# mainboard.net
KiCad netlist of a schematic drawn in EAGLE
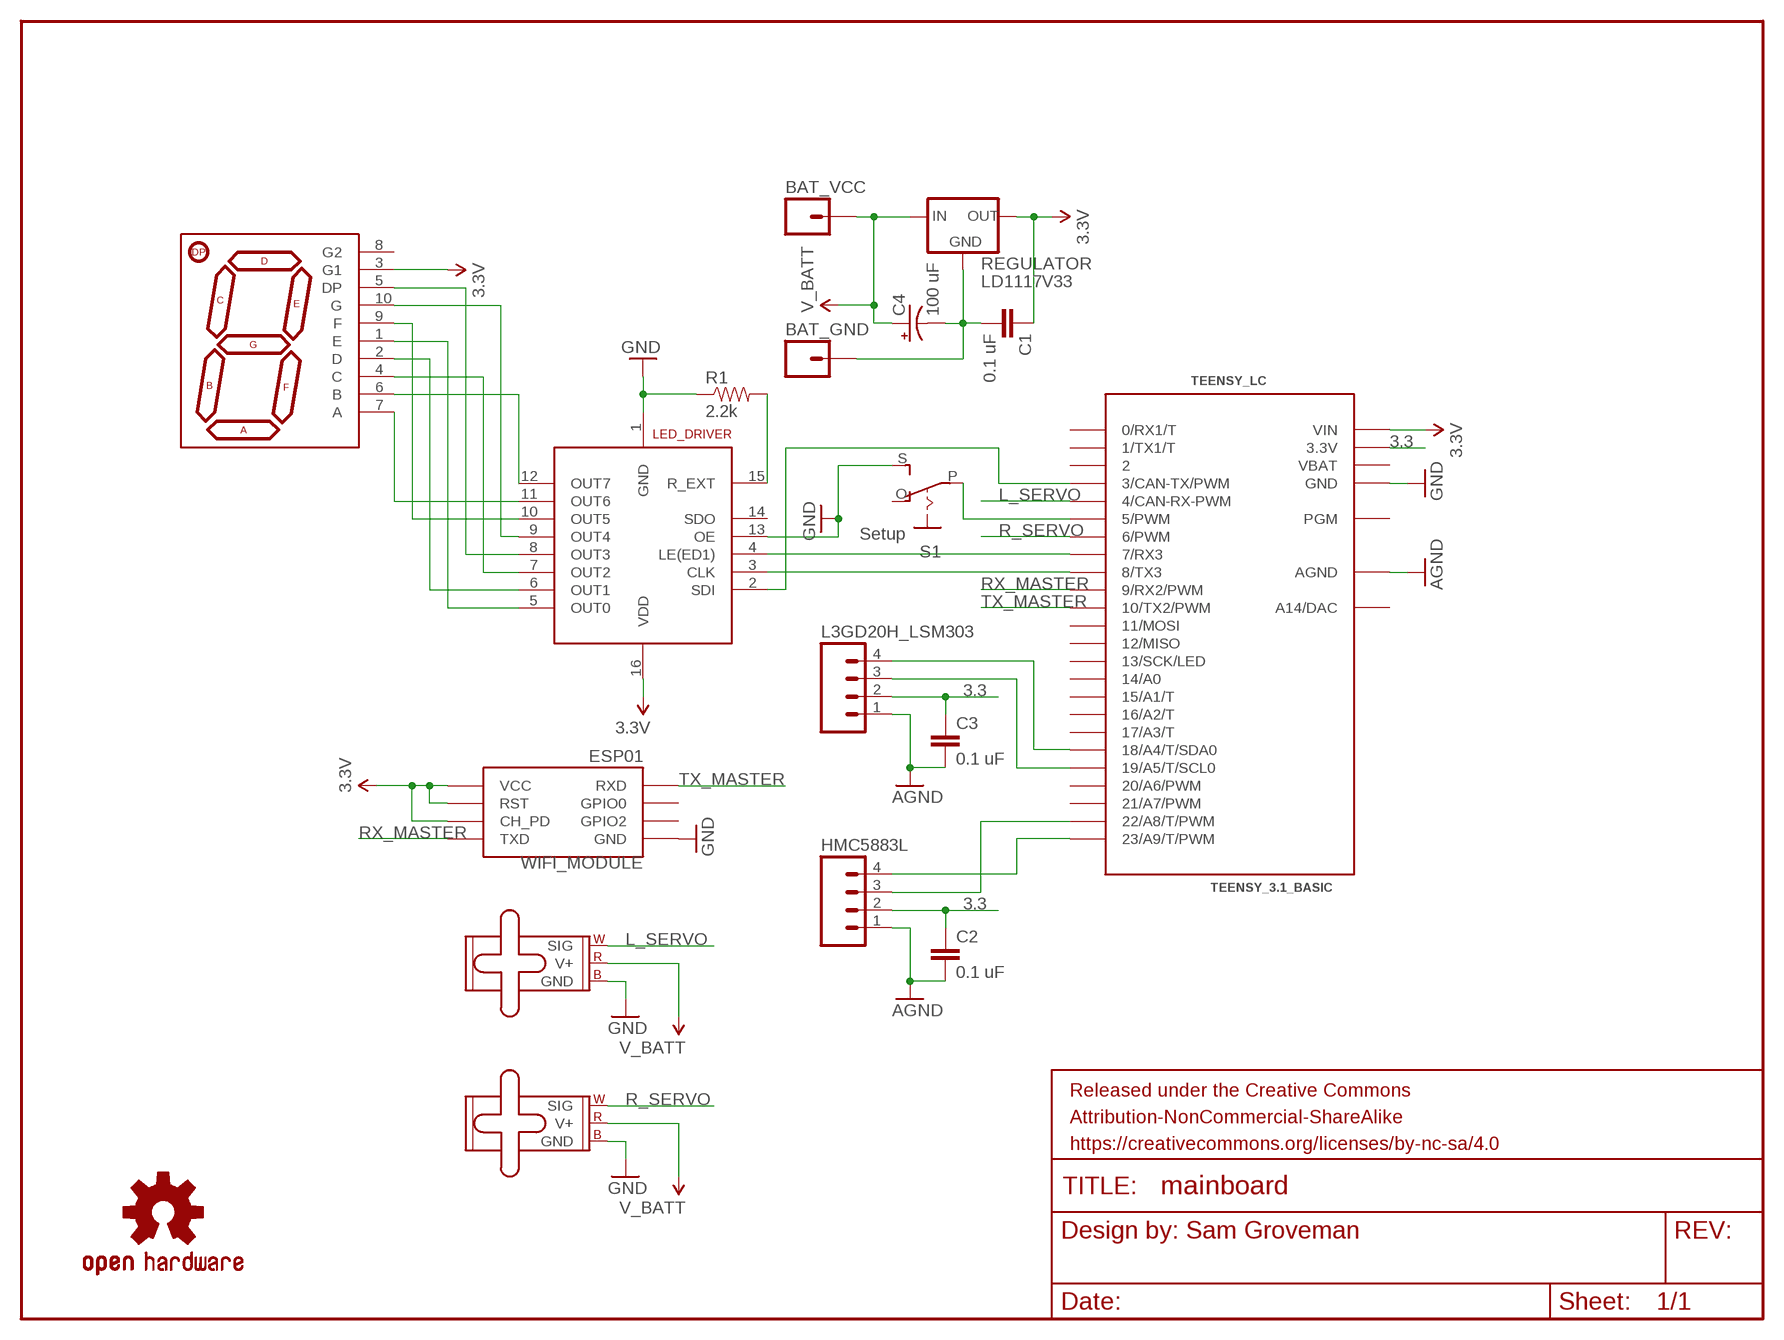
[diagram p0: schematic, sheet 1]

(export (version "E")
  (design (tool "Eeschema 10.0.6"))
  (components
    (comp (ref "BAT_GND")
      (value "M01PTH")
      (footprint "eagle-import:1X01")
      (libsource (lib "eagle-import") (part "M01PTH"))
    )
    (comp (ref "BAT_VCC")
      (value "M01PTH")
      (footprint "eagle-import:1X01")
      (libsource (lib "eagle-import") (part "M01PTH"))
    )
    (comp (ref "C1")
      (value "0.1 uF")
      (footprint "eagle-import:CAP-PTH-SMALL")
      (libsource (lib "eagle-import") (part "CAPPTH"))
    )
    (comp (ref "C2")
      (value "0.1 uF")
      (footprint "eagle-import:CAP-PTH-SMALL")
      (libsource (lib "eagle-import") (part "CAPPTH"))
    )
    (comp (ref "C3")
      (value "0.1 uF")
      (footprint "eagle-import:CAP-PTH-SMALL")
      (libsource (lib "eagle-import") (part "CAPPTH"))
    )
    (comp (ref "C4")
      (value "100 uF")
      (footprint "eagle-import:CPOL-RADIAL-100UF-25V")
      (libsource (lib "eagle-import") (part "CAP_POLPTH1"))
    )
    (comp (ref "FRAME1")
      (value "FRAME-LETTER")
      (footprint "eagle-import:CREATIVE_COMMONS")
      (libsource (lib "eagle-import") (part "FRAME-LETTER"))
    )
    (comp (ref "HMC5883L")
      (value "M04PTH")
      (footprint "eagle-import:1X04")
      (libsource (lib "eagle-import") (part "M04PTH"))
    )
    (comp (ref "L3GD20H_LSM303")
      (value "M04PTH")
      (footprint "eagle-import:1X04")
      (libsource (lib "eagle-import") (part "M04PTH"))
    )
    (comp (ref "LED_DRIVER")
      (value "TLC5916/17DIP-16")
      (footprint "eagle-import:DIP-16")
      (libsource (lib "eagle-import") (part "TLC5916/17DIP-16"))
    )
    (comp (ref "LOGO1")
      (value "OSHW-LOGOL")
      (footprint "eagle-import:OSHW-LOGO-L")
      (libsource (lib "eagle-import") (part "OSHW-LOGOL"))
    )
    (comp (ref "L_SERVO")
      (value "SMALL_SERVO")
      (footprint "eagle-import:1X03")
      (libsource (lib "eagle-import") (part "SMALL_SERVO"))
    )
    (comp (ref "R1")
      (value "2.2k")
      (footprint "eagle-import:AXIAL-0.4")
      (libsource (lib "eagle-import") (part "RESISTORPTH-1/4W"))
    )
    (comp (ref "REGULATOR")
      (value "LD1117V33")
      (footprint "eagle-import:LD1117V33")
      (libsource (lib "eagle-import") (part "LD1117V33"))
    )
    (comp (ref "R_SERVO")
      (value "SMALL_SERVO")
      (footprint "eagle-import:1X03")
      (libsource (lib "eagle-import") (part "SMALL_SERVO"))
    )
    (comp (ref "S1")
      (value "Setup")
      (footprint "eagle-import:EG1218")
      (libsource (lib "eagle-import") (part "EG1218S"))
    )
    (comp (ref "TEENSY_LC")
      (value "TEENSY_3.1_BASIC")
      (footprint "eagle-import:TEENSY_3.1_BASIC")
      (libsource (lib "eagle-import") (part "TEENSY_3.1_BASIC"))
    )
    (comp (ref "U$4")
      (value "7-SEGMENT-DISPLAY-1\"-RED")
      (footprint "eagle-import:7-SEGMENT-1_PTH")
      (libsource (lib "eagle-import") (part "7-SEGMENT-DISPLAY-1{dblquote}-RED"))
    )
    (comp (ref "WIFI_MODULE")
      (value "ESP01")
      (footprint "eagle-import:ESP01")
      (libsource (lib "eagle-import") (part "ESP01"))
    )
  )
  (nets
    (net (code "1") (name "/3.3") (class "Default")
      (node (ref "C2") (pin "1") (pinfunction "1_1") (pintype "passive"))
      (node (ref "C3") (pin "1") (pinfunction "1_1") (pintype "passive"))
      (node (ref "HMC5883L") (pin "2") (pinfunction "2_2") (pintype "passive"))
      (node (ref "L3GD20H_LSM303") (pin "2") (pinfunction "2_2") (pintype "passive"))
      (node (ref "TEENSY_LC") (pin "3.3V") (pinfunction "3.3V_3.3V") (pintype "power_in"))
      (node (ref "TEENSY_LC") (pin "3.3V1") (pinfunction "3.3V_3.3V1") (pintype "power_in"))
    )
    (net (code "2") (name "/L_SERVO") (class "Default")
      (node (ref "L_SERVO") (pin "1") (pinfunction "SIG_1") (pintype "bidirectional"))
      (node (ref "TEENSY_LC") (pin "4") (pinfunction "4/CAN-RX-PWM_4") (pintype "bidirectional"))
    )
    (net (code "3") (name "/RX_MASTER") (class "Default")
      (node (ref "TEENSY_LC") (pin "9") (pinfunction "9/RX2/PWM_9") (pintype "bidirectional"))
      (node (ref "WIFI_MODULE") (pin "TX") (pinfunction "TXD_TX") (pintype "bidirectional"))
    )
    (net (code "4") (name "/R_SERVO") (class "Default")
      (node (ref "R_SERVO") (pin "1") (pinfunction "SIG_1") (pintype "bidirectional"))
      (node (ref "TEENSY_LC") (pin "6") (pinfunction "6/PWM_6") (pintype "bidirectional"))
    )
    (net (code "5") (name "/TX_MASTER") (class "Default")
      (node (ref "TEENSY_LC") (pin "10") (pinfunction "10/TX2/PWM_10") (pintype "bidirectional"))
      (node (ref "WIFI_MODULE") (pin "RX") (pinfunction "RXD_RX") (pintype "bidirectional"))
    )
    (net (code "6") (name "/VBAT") (class "Default")
      (node (ref "TEENSY_LC") (pin "VBAT") (pinfunction "VBAT_VBAT") (pintype "power_in"))
    )
    (net (code "7") (name "3.3V") (class "Default")
      (node (ref "C1") (pin "1") (pinfunction "1_1") (pintype "passive"))
      (node (ref "LED_DRIVER") (pin "16") (pinfunction "VDD_16") (pintype "bidirectional"))
      (node (ref "REGULATOR") (pin "OUT") (pinfunction "OUT_OUT") (pintype "output"))
      (node (ref "TEENSY_LC") (pin "VIN") (pinfunction "VIN_VIN") (pintype "power_in"))
      (node (ref "U$4") (pin "3") (pinfunction "G1_3") (pintype "bidirectional"))
      (node (ref "WIFI_MODULE") (pin "CH_PD") (pinfunction "CH_PD_CH_PD") (pintype "bidirectional"))
      (node (ref "WIFI_MODULE") (pin "RST") (pinfunction "RST_RST") (pintype "bidirectional"))
      (node (ref "WIFI_MODULE") (pin "VCC") (pinfunction "VCC_VCC") (pintype "bidirectional"))
    )
    (net (code "8") (name "AGND") (class "Default")
      (node (ref "C2") (pin "2") (pinfunction "2_2") (pintype "passive"))
      (node (ref "C3") (pin "2") (pinfunction "2_2") (pintype "passive"))
      (node (ref "HMC5883L") (pin "1") (pinfunction "1_1") (pintype "passive"))
      (node (ref "L3GD20H_LSM303") (pin "1") (pinfunction "1_1") (pintype "passive"))
      (node (ref "TEENSY_LC") (pin "AGND") (pinfunction "AGND_AGND") (pintype "power_in"))
    )
    (net (code "9") (name "GND") (class "Default")
      (node (ref "BAT_GND") (pin "1") (pinfunction "1_1") (pintype "passive"))
      (node (ref "C1") (pin "2") (pinfunction "2_2") (pintype "passive"))
      (node (ref "C4") (pin "2") (pinfunction "-_2") (pintype "passive"))
      (node (ref "LED_DRIVER") (pin "1") (pinfunction "GND_1") (pintype "bidirectional"))
      (node (ref "LED_DRIVER") (pin "13") (pinfunction "OE_13") (pintype "bidirectional"))
      (node (ref "L_SERVO") (pin "3") (pinfunction "GND_3") (pintype "bidirectional"))
      (node (ref "R1") (pin "P$1") (pinfunction "1_P$1") (pintype "passive"))
      (node (ref "REGULATOR") (pin "GND") (pinfunction "GND_GND") (pintype "input"))
      (node (ref "R_SERVO") (pin "3") (pinfunction "GND_3") (pintype "bidirectional"))
      (node (ref "S1") (pin "S") (pinfunction "S_S") (pintype "passive"))
      (node (ref "TEENSY_LC") (pin "GND") (pinfunction "GND_GND") (pintype "power_in"))
      (node (ref "TEENSY_LC") (pin "GND1") (pinfunction "GND_GND1") (pintype "power_in"))
      (node (ref "WIFI_MODULE") (pin "GND") (pinfunction "GND_GND") (pintype "bidirectional"))
    )
    (net (code "10") (name "Net-(LED_DRIVER-CLK)") (class "Default")
      (node (ref "LED_DRIVER") (pin "3") (pinfunction "CLK_3") (pintype "bidirectional"))
      (node (ref "TEENSY_LC") (pin "8") (pinfunction "8/TX3_8") (pintype "bidirectional"))
    )
    (net (code "11") (name "Net-(LED_DRIVER-LE(ED1))") (class "Default")
      (node (ref "LED_DRIVER") (pin "4") (pinfunction "LE(ED1)_4") (pintype "bidirectional"))
      (node (ref "TEENSY_LC") (pin "7") (pinfunction "7/RX3_7") (pintype "bidirectional"))
    )
    (net (code "12") (name "Net-(LED_DRIVER-OUT0)") (class "Default")
      (node (ref "LED_DRIVER") (pin "5") (pinfunction "OUT0_5") (pintype "bidirectional"))
      (node (ref "U$4") (pin "1") (pinfunction "E_1") (pintype "bidirectional"))
    )
    (net (code "13") (name "Net-(LED_DRIVER-OUT1)") (class "Default")
      (node (ref "LED_DRIVER") (pin "6") (pinfunction "OUT1_6") (pintype "bidirectional"))
      (node (ref "U$4") (pin "2") (pinfunction "D_2") (pintype "bidirectional"))
    )
    (net (code "14") (name "Net-(LED_DRIVER-OUT2)") (class "Default")
      (node (ref "LED_DRIVER") (pin "7") (pinfunction "OUT2_7") (pintype "bidirectional"))
      (node (ref "U$4") (pin "4") (pinfunction "C_4") (pintype "bidirectional"))
    )
    (net (code "15") (name "Net-(LED_DRIVER-OUT3)") (class "Default")
      (node (ref "LED_DRIVER") (pin "8") (pinfunction "OUT3_8") (pintype "bidirectional"))
      (node (ref "U$4") (pin "5") (pinfunction "DP_5") (pintype "bidirectional"))
    )
    (net (code "16") (name "Net-(LED_DRIVER-OUT4)") (class "Default")
      (node (ref "LED_DRIVER") (pin "9") (pinfunction "OUT4_9") (pintype "bidirectional"))
      (node (ref "U$4") (pin "10") (pinfunction "G_10") (pintype "bidirectional"))
    )
    (net (code "17") (name "Net-(LED_DRIVER-OUT5)") (class "Default")
      (node (ref "LED_DRIVER") (pin "10") (pinfunction "OUT5_10") (pintype "bidirectional"))
      (node (ref "U$4") (pin "9") (pinfunction "F_9") (pintype "bidirectional"))
    )
    (net (code "18") (name "Net-(LED_DRIVER-OUT6)") (class "Default")
      (node (ref "LED_DRIVER") (pin "11") (pinfunction "OUT6_11") (pintype "bidirectional"))
      (node (ref "U$4") (pin "7") (pinfunction "A_7") (pintype "bidirectional"))
    )
    (net (code "19") (name "Net-(LED_DRIVER-OUT7)") (class "Default")
      (node (ref "LED_DRIVER") (pin "12") (pinfunction "OUT7_12") (pintype "bidirectional"))
      (node (ref "U$4") (pin "6") (pinfunction "B_6") (pintype "bidirectional"))
    )
    (net (code "20") (name "Net-(LED_DRIVER-R_EXT)") (class "Default")
      (node (ref "LED_DRIVER") (pin "15") (pinfunction "R_EXT_15") (pintype "bidirectional"))
      (node (ref "R1") (pin "P$2") (pinfunction "2_P$2") (pintype "passive"))
    )
    (net (code "21") (name "Net-(LED_DRIVER-SDI)") (class "Default")
      (node (ref "LED_DRIVER") (pin "2") (pinfunction "SDI_2") (pintype "bidirectional"))
      (node (ref "TEENSY_LC") (pin "3") (pinfunction "3/CAN-TX/PWM_3") (pintype "bidirectional"))
    )
    (net (code "22") (name "Net-(TEENSY_LC-5{slash}PWM)") (class "Default")
      (node (ref "S1") (pin "P") (pinfunction "P_P") (pintype "passive"))
      (node (ref "TEENSY_LC") (pin "5") (pinfunction "5/PWM_5") (pintype "bidirectional"))
    )
    (net (code "23") (name "Net-(TEENSY_LC-18{slash}A4{slash}T{slash}SDA0)") (class "Default")
      (node (ref "L3GD20H_LSM303") (pin "4") (pinfunction "4_4") (pintype "passive"))
      (node (ref "TEENSY_LC") (pin "18/A4") (pinfunction "18/A4/T/SDA0_18/A4") (pintype "bidirectional"))
    )
    (net (code "24") (name "Net-(TEENSY_LC-19{slash}A5{slash}T{slash}SCL0)") (class "Default")
      (node (ref "L3GD20H_LSM303") (pin "3") (pinfunction "3_3") (pintype "passive"))
      (node (ref "TEENSY_LC") (pin "19/A5") (pinfunction "19/A5/T/SCL0_19/A5") (pintype "bidirectional"))
    )
    (net (code "25") (name "Net-(TEENSY_LC-22{slash}A8{slash}T{slash}PWM)") (class "Default")
      (node (ref "HMC5883L") (pin "3") (pinfunction "3_3") (pintype "passive"))
      (node (ref "TEENSY_LC") (pin "22/A8") (pinfunction "22/A8/T/PWM_22/A8") (pintype "bidirectional"))
    )
    (net (code "26") (name "Net-(TEENSY_LC-23{slash}A9{slash}T{slash}PWM)") (class "Default")
      (node (ref "HMC5883L") (pin "4") (pinfunction "4_4") (pintype "passive"))
      (node (ref "TEENSY_LC") (pin "23/A9") (pinfunction "23/A9/T/PWM_23/A9") (pintype "bidirectional"))
    )
    (net (code "27") (name "V_BATT") (class "Default")
      (node (ref "BAT_VCC") (pin "1") (pinfunction "1_1") (pintype "passive"))
      (node (ref "C4") (pin "1") (pinfunction "+_1") (pintype "passive"))
      (node (ref "L_SERVO") (pin "2") (pinfunction "V+_2") (pintype "bidirectional"))
      (node (ref "REGULATOR") (pin "IN") (pinfunction "IN_IN") (pintype "input"))
      (node (ref "R_SERVO") (pin "2") (pinfunction "V+_2") (pintype "bidirectional"))
    )
    (net (code "28") (name "unconnected-(LED_DRIVER-SDO-Pad14)") (class "Default")
      (node (ref "LED_DRIVER") (pin "14") (pinfunction "SDO_14") (pintype "bidirectional"))
    )
    (net (code "29") (name "unconnected-(S1-PadO)") (class "Default")
      (node (ref "S1") (pin "O") (pinfunction "O_O") (pintype "passive"))
    )
    (net (code "30") (name "unconnected-(TEENSY_LC-0{slash}RX1{slash}T-Pad0)") (class "Default")
      (node (ref "TEENSY_LC") (pin "0") (pinfunction "0/RX1/T_0") (pintype "bidirectional"))
    )
    (net (code "31") (name "unconnected-(TEENSY_LC-1{slash}TX1{slash}T-Pad1)") (class "Default")
      (node (ref "TEENSY_LC") (pin "1") (pinfunction "1/TX1/T_1") (pintype "bidirectional"))
    )
    (net (code "32") (name "unconnected-(TEENSY_LC-11{slash}MOSI-Pad11)") (class "Default")
      (node (ref "TEENSY_LC") (pin "11") (pinfunction "11/MOSI_11") (pintype "bidirectional"))
    )
    (net (code "33") (name "unconnected-(TEENSY_LC-12{slash}MISO-Pad12)") (class "Default")
      (node (ref "TEENSY_LC") (pin "12") (pinfunction "12/MISO_12") (pintype "bidirectional"))
    )
    (net (code "34") (name "unconnected-(TEENSY_LC-13{slash}SCK{slash}LED-Pad13)") (class "Default")
      (node (ref "TEENSY_LC") (pin "13") (pinfunction "13/SCK/LED_13") (pintype "bidirectional"))
    )
    (net (code "35") (name "unconnected-(TEENSY_LC-15{slash}A1{slash}T-Pad15{slash}A1)") (class "Default")
      (node (ref "TEENSY_LC") (pin "15/A1") (pinfunction "15/A1/T_15/A1") (pintype "bidirectional"))
    )
    (net (code "36") (name "unconnected-(TEENSY_LC-16{slash}A2{slash}T-Pad16{slash}A2)") (class "Default")
      (node (ref "TEENSY_LC") (pin "16/A2") (pinfunction "16/A2/T_16/A2") (pintype "bidirectional"))
    )
    (net (code "37") (name "unconnected-(TEENSY_LC-17{slash}A3{slash}T-Pad17{slash}A3)") (class "Default")
      (node (ref "TEENSY_LC") (pin "17/A3") (pinfunction "17/A3/T_17/A3") (pintype "bidirectional"))
    )
    (net (code "38") (name "unconnected-(TEENSY_LC-20{slash}A6{slash}PWM-Pad20{slash}A6)") (class "Default")
      (node (ref "TEENSY_LC") (pin "20/A6") (pinfunction "20/A6/PWM_20/A6") (pintype "bidirectional"))
    )
    (net (code "39") (name "unconnected-(TEENSY_LC-21{slash}A7{slash}PWM-Pad21{slash}A7)") (class "Default")
      (node (ref "TEENSY_LC") (pin "21/A7") (pinfunction "21/A7/PWM_21/A7") (pintype "bidirectional"))
    )
    (net (code "40") (name "unconnected-(TEENSY_LC-A14{slash}DAC-PadA14)") (class "Default")
      (node (ref "TEENSY_LC") (pin "A14") (pinfunction "A14/DAC_A14") (pintype "bidirectional"))
    )
    (net (code "41") (name "unconnected-(TEENSY_LC-Pad2)") (class "Default")
      (node (ref "TEENSY_LC") (pin "2") (pinfunction "2_2") (pintype "bidirectional"))
    )
    (net (code "42") (name "unconnected-(TEENSY_LC-Pad14{slash}A0)") (class "Default")
      (node (ref "TEENSY_LC") (pin "14/A0") (pinfunction "14/A0_14/A0") (pintype "bidirectional"))
    )
    (net (code "43") (name "unconnected-(TEENSY_LC-PadPGM)") (class "Default")
      (node (ref "TEENSY_LC") (pin "PGM") (pinfunction "PGM_PGM") (pintype "bidirectional"))
    )
    (net (code "44") (name "unconnected-(U$4-G2-Pad8)") (class "Default")
      (node (ref "U$4") (pin "8") (pinfunction "G2_8") (pintype "bidirectional"))
    )
    (net (code "45") (name "unconnected-(WIFI_MODULE-PadGPIO0)") (class "Default")
      (node (ref "WIFI_MODULE") (pin "GPIO0") (pinfunction "GPIO0_GPIO0") (pintype "bidirectional"))
    )
    (net (code "46") (name "unconnected-(WIFI_MODULE-PadGPIO2)") (class "Default")
      (node (ref "WIFI_MODULE") (pin "GPIO2") (pinfunction "GPIO2_GPIO2") (pintype "bidirectional"))
    )
  )
)
